# BMFlexFuel_V1_2.net
KiCad netlist of a schematic drawn in EAGLE
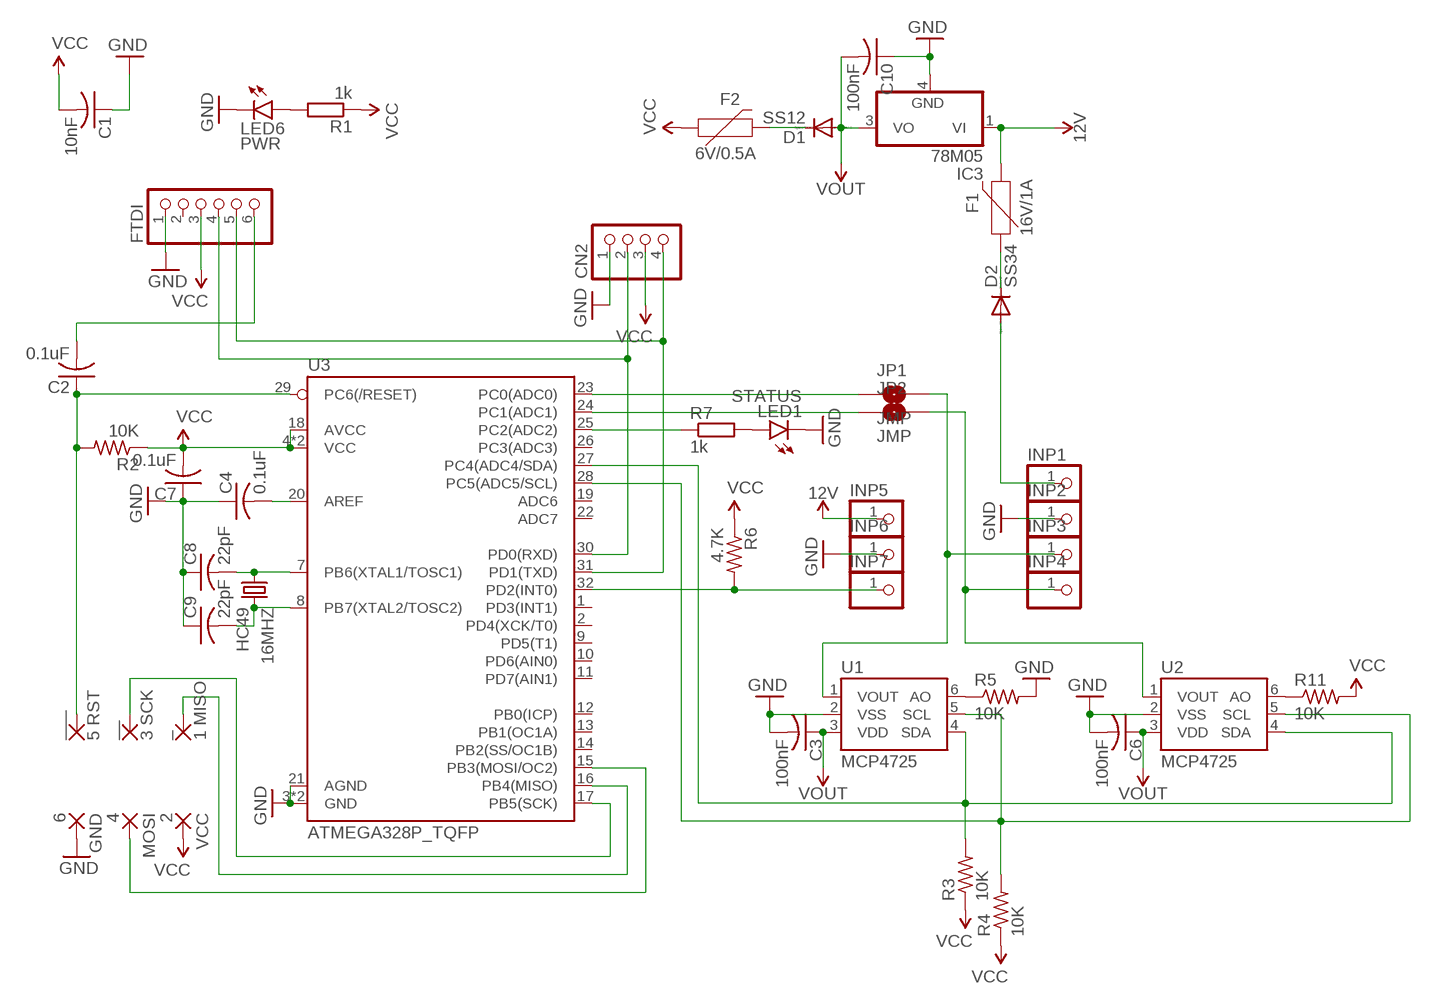
[diagram p0: schematic, sheet 1]

(export (version "E")
  (design (tool "Eeschema 10.0.6"))
  (components
    (comp (ref "16MHZ")
      (value "HC49")
      (footprint "eagle-import:HC49")
      (libsource (lib "eagle-import") (part "CRYSTALS-NOGND-HC49"))
    )
    (comp (ref "C1")
      (value "10nF")
      (footprint "eagle-import:C1206")
      (libsource (lib "eagle-import") (part "C-USC1206"))
    )
    (comp (ref "C2")
      (value "0.1uF")
      (footprint "eagle-import:C0603")
      (libsource (lib "eagle-import") (part "C-USC0603"))
    )
    (comp (ref "C3")
      (value "100nF")
      (footprint "eagle-import:C0603")
      (libsource (lib "eagle-import") (part "C-USC0603"))
    )
    (comp (ref "C4")
      (value "0.1uF")
      (footprint "eagle-import:C0603")
      (libsource (lib "eagle-import") (part "C-USC0603"))
    )
    (comp (ref "C6")
      (value "100nF")
      (footprint "eagle-import:C0603")
      (libsource (lib "eagle-import") (part "C-USC0603"))
    )
    (comp (ref "C7")
      (value "0.1uF")
      (footprint "eagle-import:C0603")
      (libsource (lib "eagle-import") (part "C-USC0603"))
    )
    (comp (ref "C8")
      (value "22pF")
      (footprint "eagle-import:C0603")
      (libsource (lib "eagle-import") (part "C-USC0603"))
    )
    (comp (ref "C9")
      (value "22pF")
      (footprint "eagle-import:C0603")
      (libsource (lib "eagle-import") (part "C-USC0603"))
    )
    (comp (ref "C10")
      (value "100nF")
      (footprint "eagle-import:C0603")
      (libsource (lib "eagle-import") (part "C-USC0603"))
    )
    (comp (ref "CN2")
      (value "PINHD-1X4")
      (footprint "eagle-import:1X04")
      (libsource (lib "eagle-import") (part "PINHD-1X4"))
    )
    (comp (ref "D1")
      (value "SS12")
      (footprint "eagle-import:DO214AC")
      (libsource (lib "eagle-import") (part "DIODE-DO214AC"))
    )
    (comp (ref "D2")
      (value "SS34")
      (footprint "eagle-import:DO214AC")
      (libsource (lib "eagle-import") (part "DIODE-DO214AC"))
    )
    (comp (ref "F1")
      (value "16V/1A")
      (footprint "eagle-import:1206")
      (libsource (lib "eagle-import") (part "PPTC_HALF-AMP"))
    )
    (comp (ref "F2")
      (value "6V/0.5A")
      (footprint "eagle-import:1206")
      (libsource (lib "eagle-import") (part "PPTC_HALF-AMP"))
    )
    (comp (ref "FTDI")
      (value "PINHD-1X6")
      (footprint "eagle-import:1X06")
      (libsource (lib "eagle-import") (part "PINHD-1X6"))
    )
    (comp (ref "GND")
      (value "6")
      (footprint "eagle-import:SMD1,27-2,54")
      (libsource (lib "eagle-import") (part "SMD2"))
    )
    (comp (ref "IC3")
      (value "78M05")
      (footprint "eagle-import:DPACK_3")
      (libsource (lib "eagle-import") (part "MC78M05ABDT"))
    )
    (comp (ref "INP1")
      (value "PINHD-1X1_LARGE")
      (footprint "eagle-import:1X01_LARGE")
      (libsource (lib "eagle-import") (part "PINHD-1X1_LARGE"))
    )
    (comp (ref "INP2")
      (value "PINHD-1X1_LARGE")
      (footprint "eagle-import:1X01_LARGE")
      (libsource (lib "eagle-import") (part "PINHD-1X1_LARGE"))
    )
    (comp (ref "INP3")
      (value "PINHD-1X1_LARGE")
      (footprint "eagle-import:1X01_LARGE")
      (libsource (lib "eagle-import") (part "PINHD-1X1_LARGE"))
    )
    (comp (ref "INP4")
      (value "PINHD-1X1_LARGE")
      (footprint "eagle-import:1X01_LARGE")
      (libsource (lib "eagle-import") (part "PINHD-1X1_LARGE"))
    )
    (comp (ref "INP5")
      (value "PINHD-1X1_LARGE")
      (footprint "eagle-import:1X01_LARGE")
      (libsource (lib "eagle-import") (part "PINHD-1X1_LARGE"))
    )
    (comp (ref "INP6")
      (value "PINHD-1X1_LARGE")
      (footprint "eagle-import:1X01_LARGE")
      (libsource (lib "eagle-import") (part "PINHD-1X1_LARGE"))
    )
    (comp (ref "INP7")
      (value "PINHD-1X1_LARGE")
      (footprint "eagle-import:1X01_LARGE")
      (libsource (lib "eagle-import") (part "PINHD-1X1_LARGE"))
    )
    (comp (ref "JP1")
      (value "JMP")
      (footprint "eagle-import:SMT-JUMPER_2_NO_NO-SILK")
      (libsource (lib "eagle-import") (part "JUMPER-SMT_2_NO_NO-SILK"))
    )
    (comp (ref "JP2")
      (value "JMP")
      (footprint "eagle-import:SMT-JUMPER_2_NO_NO-SILK")
      (libsource (lib "eagle-import") (part "JUMPER-SMT_2_NO_NO-SILK"))
    )
    (comp (ref "LED1")
      (value "STATUS")
      (footprint "eagle-import:CHIPLED_0805")
      (libsource (lib "eagle-import") (part "LEDCHIPLED_0805"))
    )
    (comp (ref "LED6")
      (value "PWR")
      (footprint "eagle-import:CHIPLED_0805")
      (libsource (lib "eagle-import") (part "LEDCHIPLED_0805"))
    )
    (comp (ref "MOSI")
      (value "4")
      (footprint "eagle-import:SMD1,27-2,54")
      (libsource (lib "eagle-import") (part "SMD2"))
    )
    (comp (ref "R1")
      (value "1k")
      (footprint "eagle-import:R0603")
      (libsource (lib "eagle-import") (part "R-EU_R0603"))
    )
    (comp (ref "R2")
      (value "10K")
      (footprint "eagle-import:R0603@1")
      (libsource (lib "eagle-import") (part "R-US_R0603"))
    )
    (comp (ref "R3")
      (value "10K")
      (footprint "eagle-import:R0603@1")
      (libsource (lib "eagle-import") (part "R-US_R0603"))
    )
    (comp (ref "R4")
      (value "10K")
      (footprint "eagle-import:R0603@1")
      (libsource (lib "eagle-import") (part "R-US_R0603"))
    )
    (comp (ref "R5")
      (value "10K")
      (footprint "eagle-import:R0603@1")
      (libsource (lib "eagle-import") (part "R-US_R0603"))
    )
    (comp (ref "R6")
      (value "4.7K")
      (footprint "eagle-import:R0603@1")
      (libsource (lib "eagle-import") (part "R-US_R0603"))
    )
    (comp (ref "R7")
      (value "1k")
      (footprint "eagle-import:R0603")
      (libsource (lib "eagle-import") (part "R-EU_R0603"))
    )
    (comp (ref "R11")
      (value "10K")
      (footprint "eagle-import:R0603@1")
      (libsource (lib "eagle-import") (part "R-US_R0603"))
    )
    (comp (ref "U1")
      (value "MCP4725")
      (footprint "eagle-import:SOT23-6")
      (libsource (lib "eagle-import") (part "MCP4725SOT-23"))
    )
    (comp (ref "U2")
      (value "MCP4725")
      (footprint "eagle-import:SOT23-6")
      (libsource (lib "eagle-import") (part "MCP4725SOT-23"))
    )
    (comp (ref "U3")
      (value "ATMEGA328P_TQFP")
      (footprint "eagle-import:TQFP32-08")
      (libsource (lib "eagle-import") (part "ATMEGA328P_TQFP"))
    )
    (comp (ref "VCC")
      (value "2")
      (footprint "eagle-import:SMD1,27-2,54")
      (libsource (lib "eagle-import") (part "SMD2"))
    )
    (comp (ref "_")
      (value "1 MISO")
      (footprint "eagle-import:SMD1,27-2,54")
      (libsource (lib "eagle-import") (part "SMD2"))
    )
    (comp (ref "__")
      (value "3 SCK")
      (footprint "eagle-import:SMD1,27-2,54")
      (libsource (lib "eagle-import") (part "SMD2"))
    )
    (comp (ref "___")
      (value "5 RST")
      (footprint "eagle-import:SMD1,27-2,54")
      (libsource (lib "eagle-import") (part "SMD2"))
    )
  )
  (nets
    (net (code "1") (name "12V") (class "Default")
      (node (ref "F1") (pin "2") (pinfunction "2_2") (pintype "bidirectional"))
      (node (ref "IC3") (pin "1") (pinfunction "VI_1") (pintype "input"))
      (node (ref "INP5") (pin "1") (pinfunction "1_1") (pintype "passive"))
    )
    (net (code "2") (name "GND") (class "Default")
      (node (ref "C1") (pin "1") (pinfunction "1_1") (pintype "passive"))
      (node (ref "C10") (pin "1") (pinfunction "1_1") (pintype "passive"))
      (node (ref "C3") (pin "2") (pinfunction "2_2") (pintype "passive"))
      (node (ref "C4") (pin "1") (pinfunction "1_1") (pintype "passive"))
      (node (ref "C6") (pin "2") (pinfunction "2_2") (pintype "passive"))
      (node (ref "C7") (pin "1") (pinfunction "1_1") (pintype "passive"))
      (node (ref "C8") (pin "1") (pinfunction "1_1") (pintype "passive"))
      (node (ref "C9") (pin "1") (pinfunction "1_1") (pintype "passive"))
      (node (ref "CN2") (pin "1") (pinfunction "1_1") (pintype "passive"))
      (node (ref "FTDI") (pin "1") (pinfunction "1_1") (pintype "passive"))
      (node (ref "GND") (pin "1") (pinfunction "P_1") (pintype "passive"))
      (node (ref "IC3") (pin "4") (pinfunction "GND_4") (pintype "passive"))
      (node (ref "INP2") (pin "1") (pinfunction "1_1") (pintype "passive"))
      (node (ref "INP6") (pin "1") (pinfunction "1_1") (pintype "passive"))
      (node (ref "LED1") (pin "C") (pinfunction "C_C") (pintype "passive"))
      (node (ref "LED6") (pin "C") (pinfunction "C_C") (pintype "passive"))
      (node (ref "R5") (pin "2") (pinfunction "2_2") (pintype "passive"))
      (node (ref "U1") (pin "2") (pinfunction "VSS_2") (pintype "bidirectional"))
      (node (ref "U2") (pin "2") (pinfunction "VSS_2") (pintype "bidirectional"))
      (node (ref "U3") (pin "21") (pinfunction "AGND_21") (pintype "bidirectional"))
      (node (ref "U3") (pin "3") (pinfunction "GND_3") (pintype "bidirectional"))
      (node (ref "U3") (pin "5") (pinfunction "GND_5") (pintype "bidirectional"))
    )
    (net (code "3") (name "Net-(C2-Pad2)") (class "Default")
      (node (ref "C2") (pin "2") (pinfunction "2_2") (pintype "passive"))
      (node (ref "FTDI") (pin "6") (pinfunction "6_6") (pintype "passive"))
    )
    (net (code "4") (name "Net-(D1-PadC)") (class "Default")
      (node (ref "D1") (pin "C") (pinfunction "C_C") (pintype "passive"))
      (node (ref "F2") (pin "2") (pinfunction "2_2") (pintype "bidirectional"))
    )
    (net (code "5") (name "Net-(D2-PadA)") (class "Default")
      (node (ref "D2") (pin "A") (pinfunction "A_A") (pintype "passive"))
      (node (ref "INP1") (pin "1") (pinfunction "1_1") (pintype "passive"))
    )
    (net (code "6") (name "Net-(D2-PadC)") (class "Default")
      (node (ref "D2") (pin "C") (pinfunction "C_C") (pintype "passive"))
      (node (ref "F1") (pin "1") (pinfunction "1_1") (pintype "bidirectional"))
    )
    (net (code "7") (name "Net-(LED1-PadA)") (class "Default")
      (node (ref "LED1") (pin "A") (pinfunction "A_A") (pintype "passive"))
      (node (ref "R7") (pin "2") (pinfunction "2_2") (pintype "passive"))
    )
    (net (code "8") (name "Net-(LED6-PadA)") (class "Default")
      (node (ref "LED6") (pin "A") (pinfunction "A_A") (pintype "passive"))
      (node (ref "R1") (pin "2") (pinfunction "2_2") (pintype "passive"))
    )
    (net (code "9") (name "Net-(MOSI-P)") (class "Default")
      (node (ref "MOSI") (pin "1") (pinfunction "P_1") (pintype "passive"))
      (node (ref "U3") (pin "15") (pinfunction "PB3(MOSI/OC2)_15") (pintype "bidirectional"))
    )
    (net (code "10") (name "Net-(U1-AO)") (class "Default")
      (node (ref "R5") (pin "1") (pinfunction "1_1") (pintype "passive"))
      (node (ref "U1") (pin "6") (pinfunction "AO_6") (pintype "bidirectional"))
    )
    (net (code "11") (name "Net-(U1-SCL)") (class "Default")
      (node (ref "R4") (pin "2") (pinfunction "2_2") (pintype "passive"))
      (node (ref "U1") (pin "5") (pinfunction "SCL_5") (pintype "bidirectional"))
      (node (ref "U2") (pin "5") (pinfunction "SCL_5") (pintype "bidirectional"))
      (node (ref "U3") (pin "28") (pinfunction "PC5(ADC5/SCL)_28") (pintype "bidirectional"))
    )
    (net (code "12") (name "Net-(U1-SDA)") (class "Default")
      (node (ref "R3") (pin "2") (pinfunction "2_2") (pintype "passive"))
      (node (ref "U1") (pin "4") (pinfunction "SDA_4") (pintype "bidirectional"))
      (node (ref "U2") (pin "4") (pinfunction "SDA_4") (pintype "bidirectional"))
      (node (ref "U3") (pin "27") (pinfunction "PC4(ADC4/SDA)_27") (pintype "bidirectional"))
    )
    (net (code "13") (name "Net-(U1-VOUT)") (class "Default")
      (node (ref "INP3") (pin "1") (pinfunction "1_1") (pintype "passive"))
      (node (ref "JP1") (pin "2") (pinfunction "2_2") (pintype "passive"))
      (node (ref "U1") (pin "1") (pinfunction "VOUT_1") (pintype "bidirectional"))
    )
    (net (code "14") (name "Net-(U2-AO)") (class "Default")
      (node (ref "R11") (pin "1") (pinfunction "1_1") (pintype "passive"))
      (node (ref "U2") (pin "6") (pinfunction "AO_6") (pintype "bidirectional"))
    )
    (net (code "15") (name "Net-(U2-VOUT)") (class "Default")
      (node (ref "INP4") (pin "1") (pinfunction "1_1") (pintype "passive"))
      (node (ref "JP2") (pin "2") (pinfunction "2_2") (pintype "passive"))
      (node (ref "U2") (pin "1") (pinfunction "VOUT_1") (pintype "bidirectional"))
    )
    (net (code "16") (name "Net-(U3-AREF)") (class "Default")
      (node (ref "C4") (pin "2") (pinfunction "2_2") (pintype "passive"))
      (node (ref "U3") (pin "20") (pinfunction "AREF_20") (pintype "bidirectional"))
    )
    (net (code "17") (name "Net-(U3-PB4(MISO))") (class "Default")
      (node (ref "U3") (pin "16") (pinfunction "PB4(MISO)_16") (pintype "bidirectional"))
      (node (ref "_") (pin "1") (pinfunction "P_1") (pintype "passive"))
    )
    (net (code "18") (name "Net-(U3-PB5(SCK))") (class "Default")
      (node (ref "U3") (pin "17") (pinfunction "PB5(SCK)_17") (pintype "bidirectional"))
      (node (ref "__") (pin "1") (pinfunction "P_1") (pintype "passive"))
    )
    (net (code "19") (name "Net-(U3-PB6(XTAL1{slash}TOSC1))") (class "Default")
      (node (ref "16MHZ") (pin "1") (pinfunction "1_1") (pintype "passive"))
      (node (ref "C8") (pin "2") (pinfunction "2_2") (pintype "passive"))
      (node (ref "U3") (pin "7") (pinfunction "PB6(XTAL1/TOSC1)_7") (pintype "bidirectional"))
    )
    (net (code "20") (name "Net-(U3-PB7(XTAL2{slash}TOSC2))") (class "Default")
      (node (ref "16MHZ") (pin "2") (pinfunction "2_2") (pintype "passive"))
      (node (ref "C9") (pin "2") (pinfunction "2_2") (pintype "passive"))
      (node (ref "U3") (pin "8") (pinfunction "PB7(XTAL2/TOSC2)_8") (pintype "bidirectional"))
    )
    (net (code "21") (name "Net-(U3-PC0(ADC0))") (class "Default")
      (node (ref "JP1") (pin "1") (pinfunction "1_1") (pintype "passive"))
      (node (ref "U3") (pin "23") (pinfunction "PC0(ADC0)_23") (pintype "bidirectional"))
    )
    (net (code "22") (name "Net-(U3-PC1(ADC1))") (class "Default")
      (node (ref "JP2") (pin "1") (pinfunction "1_1") (pintype "passive"))
      (node (ref "U3") (pin "24") (pinfunction "PC1(ADC1)_24") (pintype "bidirectional"))
    )
    (net (code "23") (name "Net-(U3-PC2(ADC2))") (class "Default")
      (node (ref "R7") (pin "1") (pinfunction "1_1") (pintype "passive"))
      (node (ref "U3") (pin "25") (pinfunction "PC2(ADC2)_25") (pintype "bidirectional"))
    )
    (net (code "24") (name "Net-(U3-PC6({slash}RESET))") (class "Default")
      (node (ref "C2") (pin "1") (pinfunction "1_1") (pintype "passive"))
      (node (ref "R2") (pin "2") (pinfunction "2_2") (pintype "passive"))
      (node (ref "U3") (pin "29") (pinfunction "PC6(/RESET)_29") (pintype "bidirectional"))
      (node (ref "___") (pin "1") (pinfunction "P_1") (pintype "passive"))
    )
    (net (code "25") (name "Net-(U3-PD0(RXD))") (class "Default")
      (node (ref "CN2") (pin "2") (pinfunction "2_2") (pintype "passive"))
      (node (ref "FTDI") (pin "4") (pinfunction "4_4") (pintype "passive"))
      (node (ref "U3") (pin "30") (pinfunction "PD0(RXD)_30") (pintype "bidirectional"))
    )
    (net (code "26") (name "Net-(U3-PD1(TXD))") (class "Default")
      (node (ref "CN2") (pin "4") (pinfunction "4_4") (pintype "passive"))
      (node (ref "FTDI") (pin "5") (pinfunction "5_5") (pintype "passive"))
      (node (ref "U3") (pin "31") (pinfunction "PD1(TXD)_31") (pintype "bidirectional"))
    )
    (net (code "27") (name "Net-(U3-PD2(INT0))") (class "Default")
      (node (ref "INP7") (pin "1") (pinfunction "1_1") (pintype "passive"))
      (node (ref "R6") (pin "2") (pinfunction "2_2") (pintype "passive"))
      (node (ref "U3") (pin "32") (pinfunction "PD2(INT0)_32") (pintype "bidirectional"))
    )
    (net (code "28") (name "VCC") (class "Default")
      (node (ref "C1") (pin "2") (pinfunction "2_2") (pintype "passive"))
      (node (ref "C7") (pin "2") (pinfunction "2_2") (pintype "passive"))
      (node (ref "CN2") (pin "3") (pinfunction "3_3") (pintype "passive"))
      (node (ref "F2") (pin "1") (pinfunction "1_1") (pintype "bidirectional"))
      (node (ref "FTDI") (pin "3") (pinfunction "3_3") (pintype "passive"))
      (node (ref "R1") (pin "1") (pinfunction "1_1") (pintype "passive"))
      (node (ref "R11") (pin "2") (pinfunction "2_2") (pintype "passive"))
      (node (ref "R2") (pin "1") (pinfunction "1_1") (pintype "passive"))
      (node (ref "R3") (pin "1") (pinfunction "1_1") (pintype "passive"))
      (node (ref "R4") (pin "1") (pinfunction "1_1") (pintype "passive"))
      (node (ref "R6") (pin "1") (pinfunction "1_1") (pintype "passive"))
      (node (ref "U3") (pin "18") (pinfunction "AVCC_18") (pintype "bidirectional"))
      (node (ref "U3") (pin "4") (pinfunction "VCC_4") (pintype "bidirectional"))
      (node (ref "U3") (pin "6") (pinfunction "VCC_6") (pintype "bidirectional"))
      (node (ref "VCC") (pin "1") (pinfunction "P_1") (pintype "passive"))
    )
    (net (code "29") (name "VOUT") (class "Default")
      (node (ref "C10") (pin "2") (pinfunction "2_2") (pintype "passive"))
      (node (ref "C3") (pin "1") (pinfunction "1_1") (pintype "passive"))
      (node (ref "C6") (pin "1") (pinfunction "1_1") (pintype "passive"))
      (node (ref "D1") (pin "A") (pinfunction "A_A") (pintype "passive"))
      (node (ref "IC3") (pin "3") (pinfunction "VO_3") (pintype "passive"))
      (node (ref "U1") (pin "3") (pinfunction "VDD_3") (pintype "bidirectional"))
      (node (ref "U2") (pin "3") (pinfunction "VDD_3") (pintype "bidirectional"))
    )
    (net (code "30") (name "unconnected-(FTDI-Pad2)") (class "Default")
      (node (ref "FTDI") (pin "2") (pinfunction "2_2") (pintype "passive"))
    )
    (net (code "31") (name "unconnected-(U3-ADC6-Pad19)") (class "Default")
      (node (ref "U3") (pin "19") (pinfunction "ADC6_19") (pintype "bidirectional"))
    )
    (net (code "32") (name "unconnected-(U3-ADC7-Pad22)") (class "Default")
      (node (ref "U3") (pin "22") (pinfunction "ADC7_22") (pintype "bidirectional"))
    )
    (net (code "33") (name "unconnected-(U3-PB0(ICP)-Pad12)") (class "Default")
      (node (ref "U3") (pin "12") (pinfunction "PB0(ICP)_12") (pintype "bidirectional"))
    )
    (net (code "34") (name "unconnected-(U3-PB1(OC1A)-Pad13)") (class "Default")
      (node (ref "U3") (pin "13") (pinfunction "PB1(OC1A)_13") (pintype "bidirectional"))
    )
    (net (code "35") (name "unconnected-(U3-PB2(SS{slash}OC1B)-Pad14)") (class "Default")
      (node (ref "U3") (pin "14") (pinfunction "PB2(SS/OC1B)_14") (pintype "bidirectional"))
    )
    (net (code "36") (name "unconnected-(U3-PC3(ADC3)-Pad26)") (class "Default")
      (node (ref "U3") (pin "26") (pinfunction "PC3(ADC3)_26") (pintype "bidirectional"))
    )
    (net (code "37") (name "unconnected-(U3-PD3(INT1)-Pad1)") (class "Default")
      (node (ref "U3") (pin "1") (pinfunction "PD3(INT1)_1") (pintype "bidirectional"))
    )
    (net (code "38") (name "unconnected-(U3-PD4(XCK{slash}T0)-Pad2)") (class "Default")
      (node (ref "U3") (pin "2") (pinfunction "PD4(XCK/T0)_2") (pintype "bidirectional"))
    )
    (net (code "39") (name "unconnected-(U3-PD5(T1)-Pad9)") (class "Default")
      (node (ref "U3") (pin "9") (pinfunction "PD5(T1)_9") (pintype "bidirectional"))
    )
    (net (code "40") (name "unconnected-(U3-PD6(AIN0)-Pad10)") (class "Default")
      (node (ref "U3") (pin "10") (pinfunction "PD6(AIN0)_10") (pintype "bidirectional"))
    )
    (net (code "41") (name "unconnected-(U3-PD7(AIN1)-Pad11)") (class "Default")
      (node (ref "U3") (pin "11") (pinfunction "PD7(AIN1)_11") (pintype "bidirectional"))
    )
  )
)
